# StEth32_Base_Power_Output.net
KiCad netlist of a schematic drawn in Altium Designer
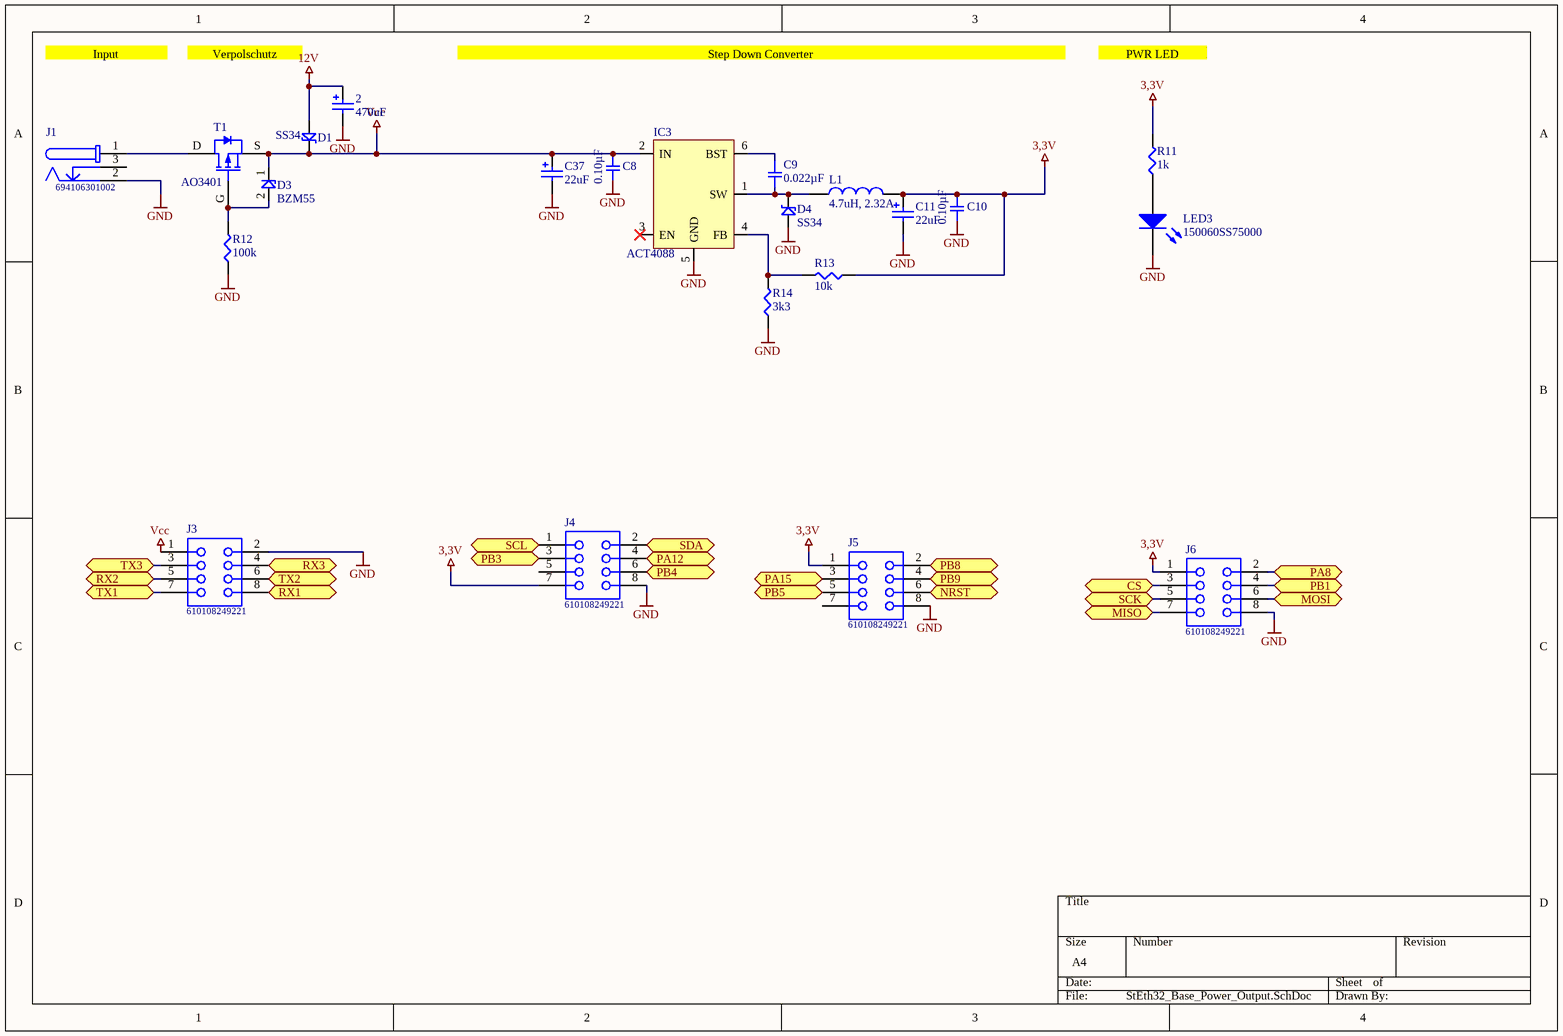
[diagram p0: StEth32_Base_Power_Output.SchDoc]

(export (version "E")
  (design (tool "Eeschema 10.0.6"))
  (components
    (comp (ref "2")
      (value "470uF")
      (footprint "WCAP-ASLI_10x10.5")
      (description "WCAP-ASLI Aluminum Electrolytic Capacitors, size Ф10x10.5mm, 25V DC, 470uF")
      (fields (field (name "PART NUMBER") "865080457015") (field (name "PUBLISHER") "Wurth Elektronik"))
      (libsource (lib "ALTIUM-WCAP-ASLI-rev17a") (part "865080457015"))
    )
    (comp (ref "C8")
      (value "0.10µF")
      (footprint "SMD-0603C")
      (description "CAP CER 0.1UF 16V X7R 0603")
      (fields
        (field (name "DIGI-KEY PART NUMBER") "490-8015-1-ND")
        (field (name "PART NUMBER") "GCM188R71C104KA37J")
      )
      (libsource (lib "capacitor_murata_0603") (part "GCM188R71C104KA37J"))
    )
    (comp (ref "C9")
      (value "0.022µF")
      (footprint "SMD-0603C")
      (description "CAP CER 0.022UF 50V X7R 0603")
      (fields
        (field (name "DIGI-KEY PART NUMBER") "490-5851-1-ND")
        (field (name "PART NUMBER") "GCJ188R71H223KA01D")
      )
      (libsource (lib "capacitor_murata_0603") (part "GCJ188R71H223KA01D"))
    )
    (comp (ref "C10")
      (value "0.10µF")
      (footprint "SMD-0603C")
      (description "CAP CER 0.1UF 16V X7R 0603")
      (fields
        (field (name "DIGI-KEY PART NUMBER") "490-8015-1-ND")
        (field (name "PART NUMBER") "GCM188R71C104KA37J")
      )
      (libsource (lib "capacitor_murata_0603") (part "GCM188R71C104KA37J"))
    )
    (comp (ref "C11")
      (value "22uF")
      (footprint "WCAP-ASLI_4x5.5")
      (description "WCAP-ASLI Aluminum Electrolytic Capacitors, size Ф4x5.5mm, 6.3V DC, 22uF")
      (fields (field (name "PART NUMBER") "865080140001") (field (name "PUBLISHER") "Wurth Elektronik"))
      (libsource (lib "ALTIUM-WCAP-ASLI-rev17a") (part "865080140001"))
    )
    (comp (ref "C37")
      (value "22uF")
      (footprint "WCAP-ASLI_4x5.5")
      (description "WCAP-ASLI Aluminum Electrolytic Capacitors, size Ф4x5.5mm, 6.3V DC, 22uF")
      (fields (field (name "PART NUMBER") "865080140001") (field (name "PUBLISHER") "Wurth Elektronik"))
      (libsource (lib "ALTIUM-WCAP-ASLI-rev17a") (part "865080140001"))
    )
    (comp (ref "D1")
      (value "SS34")
      (footprint "B240A")
      (description "Shottkydiode")
      (libsource (lib "MyLibs") (part "B240A"))
    )
    (comp (ref "D3") (value "BZM55") (footprint "SMD-0603-RES") (libsource (lib "MyLibs") (part "BZM55")))
    (comp (ref "D4")
      (value "SS34")
      (footprint "B240A")
      (description "Shottkydiode")
      (libsource (lib "MyLibs") (part "B240A"))
    )
    (comp (ref "IC3") (value "ACT4088") (footprint "SOT23-6") (libsource (lib "MyLibs") (part "ACT4088")))
    (comp (ref "J1")
      (value "694106301002")
      (footprint "694106301002")
      (description "DC Power Jack Connector WR-DC, Male, Right Angled, THT, 5 A, 24 V")
      (fields (field (name "PUBLISHER") "Wurth Elektronik"))
      (libsource (lib "694106301002_Altium_WR-DC_POWER_JACK_CONNECTORS_rev18b") (part "694106301002"))
    )
    (comp (ref "J3")
      (value "610108249221")
      (footprint "610108249221")
      (description "WR-PHD Socket Header, SMT, pitch 2.54mm, Dual Row, Angled, 8pin")
      (fields (field (name "PUBLISHER") "Wurth Elektronik"))
      (libsource (lib "o155175v243 Altium_WR-PHD (rev19a)") (part "610108249221"))
    )
    (comp (ref "J4")
      (value "610108249221")
      (footprint "610108249221")
      (description "WR-PHD Socket Header, SMT, pitch 2.54mm, Dual Row, Angled, 8pin")
      (fields (field (name "PUBLISHER") "Wurth Elektronik"))
      (libsource (lib "o155175v243 Altium_WR-PHD (rev19a)") (part "610108249221"))
    )
    (comp (ref "J5")
      (value "610108249221")
      (footprint "610108249221")
      (description "WR-PHD Socket Header, SMT, pitch 2.54mm, Dual Row, Angled, 8pin")
      (fields (field (name "PUBLISHER") "Wurth Elektronik"))
      (libsource (lib "o155175v243 Altium_WR-PHD (rev19a)") (part "610108249221"))
    )
    (comp (ref "J6")
      (value "610108249221")
      (footprint "610108249221")
      (description "WR-PHD Socket Header, SMT, pitch 2.54mm, Dual Row, Angled, 8pin")
      (fields (field (name "PUBLISHER") "Wurth Elektronik"))
      (libsource (lib "o155175v243 Altium_WR-PHD (rev19a)") (part "610108249221"))
    )
    (comp (ref "L1")
      (value "4.7uH, 2.32A")
      (footprint "WE-PD_7332")
      (description "WE-PD SMT Power Inductor, size 7332, 4.7uH, 2.32A")
      (fields (field (name "PART NUMBER") "744778004") (field (name "PUBLISHER") "Wurth Elektronik"))
      (libsource (lib "ALTIUM-WE-PD-rev19b") (part "744778004"))
    )
    (comp (ref "LED3")
      (value "150060SS75000")
      (footprint "0603_A")
      (description "SMD mono-color Chip LED, WL-SMCW, Super Red")
      (libsource (lib "WL-SMCW SMD chip LED top view mono-color waterclear") (part "150060SS75000"))
    )
    (comp (ref "R11")
      (value "1k")
      (footprint "SMD-0603-RES")
      (description "RES SMD 1K OHM 1% 1/10W 0603")
      (fields
        (field (name "PART NUMBER") "ERJ-3EKF1001V")
        (field (name "DIGI-KEY PART NUMBER") "P1.00KHCT-ND")
      )
      (libsource (lib "Panasonic_ERJ_0603") (part "ERJ-3EKF1001V"))
    )
    (comp (ref "R12")
      (value "100k")
      (footprint "SMD-0603-RES")
      (description "RES SMD 4.7K OHM 1% 1/10W 0603")
      (fields
        (field (name "PART NUMBER") "ERJ-3EKF4701V")
        (field (name "DIGI-KEY PART NUMBER") "P4.70KHCT-ND")
      )
      (libsource (lib "Panasonic_ERJ_0603") (part "ERJ-3EKF4701V"))
    )
    (comp (ref "R13")
      (value "10k")
      (footprint "SMD-0603-RES")
      (description "RES SMD 1K OHM 1% 1/10W 0603")
      (fields
        (field (name "PART NUMBER") "ERJ-3EKF1001V")
        (field (name "DIGI-KEY PART NUMBER") "P1.00KHCT-ND")
      )
      (libsource (lib "Panasonic_ERJ_0603") (part "ERJ-3EKF1001V"))
    )
    (comp (ref "R14")
      (value "3k3")
      (footprint "SMD-0603-RES")
      (description "RES SMD 1K OHM 1% 1/10W 0603")
      (fields
        (field (name "PART NUMBER") "ERJ-3EKF1001V")
        (field (name "DIGI-KEY PART NUMBER") "P1.00KHCT-ND")
      )
      (libsource (lib "Panasonic_ERJ_0603") (part "ERJ-3EKF1001V"))
    )
    (comp (ref "T1")
      (value "AO3401")
      (footprint "SOT23")
      (description "AO3401 MOSFET 30V")
      (libsource (lib "MyLibs") (part "AO3401"))
    )
  )
  (nets
    (net (code "1") (name "/CS") (class "Default")
      (node (ref "J6") (pin "3") (pinfunction "3_3") (pintype "passive"))
    )
    (net (code "2") (name "/MISO") (class "Default")
      (node (ref "J6") (pin "7") (pinfunction "7_7") (pintype "passive"))
    )
    (net (code "3") (name "/MOSI") (class "Default")
      (node (ref "J6") (pin "6") (pinfunction "6_6") (pintype "passive"))
    )
    (net (code "4") (name "/NRST") (class "Default")
      (node (ref "J5") (pin "6") (pinfunction "6_6") (pintype "passive"))
    )
    (net (code "5") (name "/PA8") (class "Default")
      (node (ref "J6") (pin "2") (pinfunction "2_2") (pintype "passive"))
    )
    (net (code "6") (name "/PA12") (class "Default")
      (node (ref "J4") (pin "4") (pinfunction "4_4") (pintype "passive"))
    )
    (net (code "7") (name "/PA15") (class "Default")
      (node (ref "J5") (pin "3") (pinfunction "3_3") (pintype "passive"))
    )
    (net (code "8") (name "/PB1") (class "Default")
      (node (ref "J6") (pin "4") (pinfunction "4_4") (pintype "passive"))
    )
    (net (code "9") (name "/PB3") (class "Default")
      (node (ref "J4") (pin "3") (pinfunction "3_3") (pintype "passive"))
    )
    (net (code "10") (name "/PB4") (class "Default")
      (node (ref "J4") (pin "6") (pinfunction "6_6") (pintype "passive"))
    )
    (net (code "11") (name "/PB5") (class "Default")
      (node (ref "J5") (pin "5") (pinfunction "5_5") (pintype "passive"))
    )
    (net (code "12") (name "/PB8") (class "Default")
      (node (ref "J5") (pin "2") (pinfunction "2_2") (pintype "passive"))
    )
    (net (code "13") (name "/PB9") (class "Default")
      (node (ref "J5") (pin "4") (pinfunction "4_4") (pintype "passive"))
    )
    (net (code "14") (name "/RX1") (class "Default")
      (node (ref "J3") (pin "8") (pinfunction "8_8") (pintype "passive"))
    )
    (net (code "15") (name "/RX2") (class "Default")
      (node (ref "J3") (pin "5") (pinfunction "5_5") (pintype "passive"))
    )
    (net (code "16") (name "/RX3") (class "Default")
      (node (ref "J3") (pin "4") (pinfunction "4_4") (pintype "passive"))
    )
    (net (code "17") (name "/SCK") (class "Default")
      (node (ref "J6") (pin "5") (pinfunction "5_5") (pintype "passive"))
    )
    (net (code "18") (name "/SCL") (class "Default")
      (node (ref "J4") (pin "1") (pinfunction "1_1") (pintype "passive"))
    )
    (net (code "19") (name "/SDA") (class "Default")
      (node (ref "J4") (pin "2") (pinfunction "2_2") (pintype "passive"))
    )
    (net (code "20") (name "/TX1") (class "Default")
      (node (ref "J3") (pin "7") (pinfunction "7_7") (pintype "passive"))
    )
    (net (code "21") (name "/TX2") (class "Default")
      (node (ref "J3") (pin "6") (pinfunction "6_6") (pintype "passive"))
    )
    (net (code "22") (name "/TX3") (class "Default")
      (node (ref "J3") (pin "3") (pinfunction "3_3") (pintype "passive"))
    )
    (net (code "23") (name "3,3V") (class "Default")
      (node (ref "C10") (pin "1") (pinfunction "1_1") (pintype "passive"))
      (node (ref "C11") (pin "1") (pinfunction "P_1") (pintype "passive"))
      (node (ref "J4") (pin "7") (pinfunction "7_7") (pintype "passive"))
      (node (ref "J5") (pin "1") (pinfunction "1_1") (pintype "passive"))
      (node (ref "J6") (pin "1") (pinfunction "1_1") (pintype "passive"))
      (node (ref "L1") (pin "2") (pinfunction "2_2") (pintype "passive"))
      (node (ref "R11") (pin "2") (pinfunction "2_2") (pintype "passive"))
      (node (ref "R13") (pin "1") (pinfunction "1_1") (pintype "passive"))
    )
    (net (code "24") (name "12V") (class "Default")
      (node (ref "2") (pin "1") (pinfunction "P_1") (pintype "passive"))
      (node (ref "D1") (pin "A") (pinfunction "A_A") (pintype "passive"))
    )
    (net (code "25") (name "GND") (class "Default")
      (node (ref "2") (pin "2") (pinfunction "N_2") (pintype "passive"))
      (node (ref "C10") (pin "2") (pinfunction "2_2") (pintype "passive"))
      (node (ref "C11") (pin "2") (pinfunction "N_2") (pintype "passive"))
      (node (ref "C37") (pin "2") (pinfunction "N_2") (pintype "passive"))
      (node (ref "C8") (pin "2") (pinfunction "2_2") (pintype "passive"))
      (node (ref "D4") (pin "A") (pinfunction "A_A") (pintype "passive"))
      (node (ref "IC3") (pin "5") (pinfunction "GND_5") (pintype "passive"))
      (node (ref "J1") (pin "2") (pinfunction "2_2") (pintype "passive"))
      (node (ref "J3") (pin "2") (pinfunction "2_2") (pintype "passive"))
      (node (ref "J4") (pin "8") (pinfunction "8_8") (pintype "passive"))
      (node (ref "J5") (pin "8") (pinfunction "8_8") (pintype "passive"))
      (node (ref "J6") (pin "8") (pinfunction "8_8") (pintype "passive"))
      (node (ref "LED3") (pin "1") (pinfunction "K_1") (pintype "passive"))
      (node (ref "R12") (pin "1") (pinfunction "1_1") (pintype "passive"))
      (node (ref "R14") (pin "1") (pinfunction "1_1") (pintype "passive"))
    )
    (net (code "26") (name "Net-(D3-1-Pad2)") (class "Default")
      (node (ref "D3") (pin "2") (pinfunction "1_2") (pintype "passive"))
      (node (ref "R12") (pin "2") (pinfunction "2_2") (pintype "passive"))
      (node (ref "T1") (pin "G") (pinfunction "G_G") (pintype "passive"))
    )
    (net (code "27") (name "Net-(IC3-BST)") (class "Default")
      (node (ref "C9") (pin "1") (pinfunction "1_1") (pintype "passive"))
      (node (ref "IC3") (pin "6") (pinfunction "BST_6") (pintype "passive"))
    )
    (net (code "28") (name "Net-(IC3-FB)") (class "Default")
      (node (ref "IC3") (pin "4") (pinfunction "FB_4") (pintype "passive"))
      (node (ref "R13") (pin "2") (pinfunction "2_2") (pintype "passive"))
      (node (ref "R14") (pin "2") (pinfunction "2_2") (pintype "passive"))
    )
    (net (code "29") (name "Net-(IC3-SW)") (class "Default")
      (node (ref "C9") (pin "2") (pinfunction "2_2") (pintype "passive"))
      (node (ref "D4") (pin "K") (pinfunction "K_K") (pintype "passive"))
      (node (ref "IC3") (pin "1") (pinfunction "SW_1") (pintype "passive"))
      (node (ref "L1") (pin "1") (pinfunction "1_1") (pintype "passive"))
    )
    (net (code "30") (name "Net-(J1-Pad1)") (class "Default")
      (node (ref "J1") (pin "1") (pinfunction "1_1") (pintype "passive"))
      (node (ref "T1") (pin "D") (pinfunction "D_D") (pintype "passive"))
    )
    (net (code "31") (name "Net-(LED3-A)") (class "Default")
      (node (ref "LED3") (pin "2") (pinfunction "A_2") (pintype "passive"))
      (node (ref "R11") (pin "1") (pinfunction "1_1") (pintype "passive"))
    )
    (net (code "32") (name "Vcc") (class "Default")
      (node (ref "C37") (pin "1") (pinfunction "P_1") (pintype "passive"))
      (node (ref "C8") (pin "1") (pinfunction "1_1") (pintype "passive"))
      (node (ref "D1") (pin "K") (pinfunction "K_K") (pintype "passive"))
      (node (ref "D3") (pin "1") (pinfunction "1_1") (pintype "passive"))
      (node (ref "IC3") (pin "2") (pinfunction "IN_2") (pintype "passive"))
      (node (ref "J3") (pin "1") (pinfunction "1_1") (pintype "passive"))
      (node (ref "T1") (pin "S") (pinfunction "S_S") (pintype "passive"))
    )
    (net (code "33") (name "unconnected-(IC3-EN-Pad3)") (class "Default")
      (node (ref "IC3") (pin "3") (pinfunction "EN_3") (pintype "passive+no_connect"))
    )
    (net (code "34") (name "unconnected-(J1-Pad3)") (class "Default")
      (node (ref "J1") (pin "3") (pinfunction "3_3") (pintype "passive"))
    )
    (net (code "35") (name "unconnected-(J4-Pad5)") (class "Default")
      (node (ref "J4") (pin "5") (pinfunction "5_5") (pintype "passive"))
    )
    (net (code "36") (name "unconnected-(J5-Pad7)") (class "Default")
      (node (ref "J5") (pin "7") (pinfunction "7_7") (pintype "passive"))
    )
  )
)
